# 5v_dc_supply.net
KiCad netlist of a schematic drawn in EAGLE
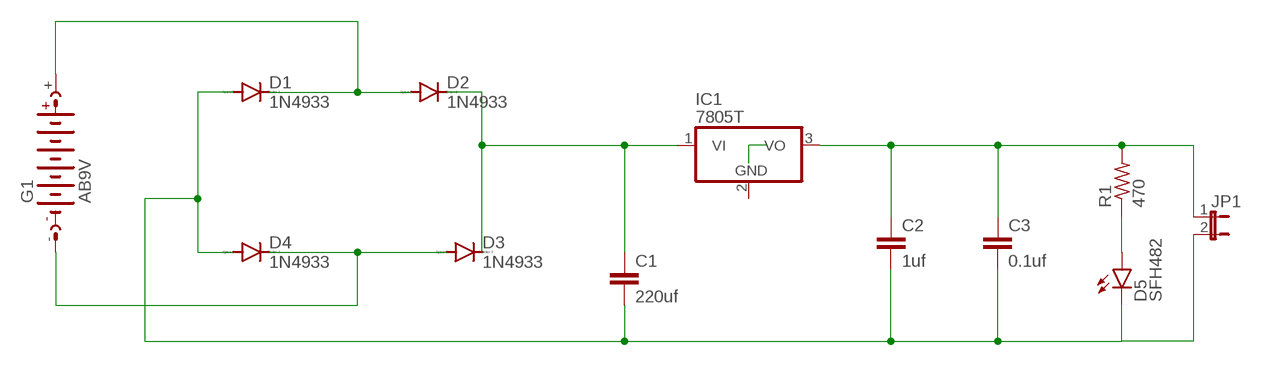
[diagram p0: schematic, sheet 1]

(export (version "E")
  (design (tool "Eeschema 10.0.6"))
  (components
    (comp (ref "C1")
      (value "220uf")
      (footprint "eagle-import:C2.5-3")
      (libsource (lib "eagle-import") (part "C2,5-3"))
    )
    (comp (ref "C2")
      (value "1uf")
      (footprint "eagle-import:C2.5-3")
      (libsource (lib "eagle-import") (part "C2,5-3"))
    )
    (comp (ref "C3")
      (value "0.1uf")
      (footprint "eagle-import:C2.5-3")
      (libsource (lib "eagle-import") (part "C2,5-3"))
    )
    (comp (ref "D1")
      (value "1N4933")
      (footprint "eagle-import:DO41-10")
      (libsource (lib "eagle-import") (part "1N4933"))
    )
    (comp (ref "D2")
      (value "1N4933")
      (footprint "eagle-import:DO41-10")
      (libsource (lib "eagle-import") (part "1N4933"))
    )
    (comp (ref "D3")
      (value "1N4933")
      (footprint "eagle-import:DO41-10")
      (libsource (lib "eagle-import") (part "1N4933"))
    )
    (comp (ref "D4")
      (value "1N4933")
      (footprint "eagle-import:DO41-10")
      (libsource (lib "eagle-import") (part "1N4933"))
    )
    (comp (ref "D5")
      (value "SFH482")
      (footprint "eagle-import:SFH482")
      (libsource (lib "eagle-import") (part "SFH482"))
    )
    (comp (ref "G1")
      (value "AB9V")
      (footprint "eagle-import:AB9V")
      (libsource (lib "eagle-import") (part "AB9V"))
    )
    (comp (ref "IC1")
      (value "7805T")
      (footprint "eagle-import:TO220H")
      (libsource (lib "eagle-import") (part "78T05"))
    )
    (comp (ref "JP1")
      (value "JP1E")
      (footprint "eagle-import:JP1")
      (libsource (lib "eagle-import") (part "JP1E"))
    )
    (comp (ref "R1")
      (value "470")
      (footprint "eagle-import:0204_7")
      (libsource (lib "eagle-import") (part "R-US_0204/7"))
    )
  )
  (nets
    (net (code "1") (name "Net-(D1-PadC)") (class "Default")
      (node (ref "D1") (pin "C") (pinfunction "C_C") (pintype "passive"))
      (node (ref "D2") (pin "A") (pinfunction "A_A") (pintype "passive"))
      (node (ref "G1") (pin "+") (pinfunction "+_+") (pintype "passive"))
    )
    (net (code "2") (name "Net-(D3-PadA)") (class "Default")
      (node (ref "D3") (pin "A") (pinfunction "A_A") (pintype "passive"))
      (node (ref "D4") (pin "C") (pinfunction "C_C") (pintype "passive"))
      (node (ref "G1") (pin "-") (pinfunction "-_-") (pintype "passive"))
    )
    (net (code "3") (name "Net-(D5-C)") (class "Default")
      (node (ref "C1") (pin "2") (pinfunction "2_2") (pintype "passive"))
      (node (ref "C2") (pin "2") (pinfunction "2_2") (pintype "passive"))
      (node (ref "C3") (pin "2") (pinfunction "2_2") (pintype "passive"))
      (node (ref "D1") (pin "A") (pinfunction "A_A") (pintype "passive"))
      (node (ref "D4") (pin "A") (pinfunction "A_A") (pintype "passive"))
      (node (ref "D5") (pin "K") (pinfunction "C_K") (pintype "passive"))
      (node (ref "JP1") (pin "2") (pinfunction "2_2") (pintype "passive"))
    )
    (net (code "4") (name "Net-(D5-PadA)") (class "Default")
      (node (ref "D5") (pin "A") (pinfunction "A_A") (pintype "passive"))
      (node (ref "R1") (pin "1") (pinfunction "1_1") (pintype "passive"))
    )
    (net (code "5") (name "Net-(IC1-VI)") (class "Default")
      (node (ref "C1") (pin "1") (pinfunction "1_1") (pintype "passive"))
      (node (ref "D2") (pin "C") (pinfunction "C_C") (pintype "passive"))
      (node (ref "D3") (pin "C") (pinfunction "C_C") (pintype "passive"))
      (node (ref "IC1") (pin "1") (pinfunction "VI_1") (pintype "input"))
    )
    (net (code "6") (name "Net-(IC1-VO)") (class "Default")
      (node (ref "C2") (pin "1") (pinfunction "1_1") (pintype "passive"))
      (node (ref "C3") (pin "1") (pinfunction "1_1") (pintype "passive"))
      (node (ref "IC1") (pin "3") (pinfunction "VO_3") (pintype "passive"))
      (node (ref "JP1") (pin "1") (pinfunction "1_1") (pintype "passive"))
      (node (ref "R1") (pin "2") (pinfunction "2_2") (pintype "passive"))
    )
    (net (code "7") (name "unconnected-(IC1-GND-Pad2)") (class "Default")
      (node (ref "IC1") (pin "2") (pinfunction "GND_2") (pintype "passive"))
    )
  )
)
